# buffered-mult.net
KiCad netlist of a schematic drawn in EAGLE
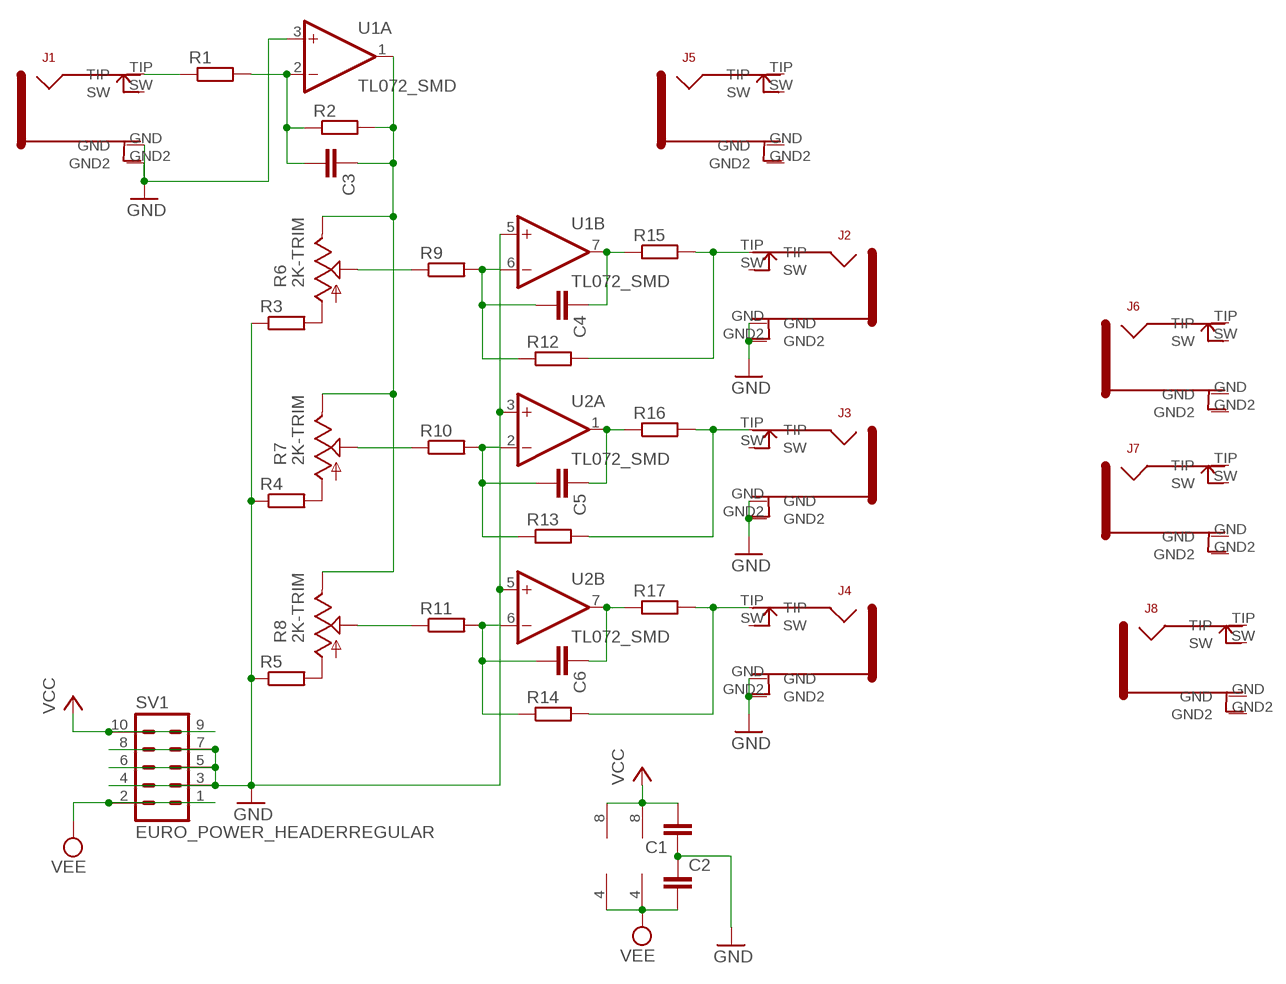
[diagram p0: schematic, sheet 1]

(export (version "E")
  (design (tool "Eeschema 10.0.6"))
  (components
    (comp (ref "C1")
      (value "C-EUC0603")
      (footprint "eagle-import:C0603")
      (libsource (lib "eagle-import") (part "C-EUC0603"))
    )
    (comp (ref "C2")
      (value "C-EUC0603")
      (footprint "eagle-import:C0603")
      (libsource (lib "eagle-import") (part "C-EUC0603"))
    )
    (comp (ref "C3")
      (value "C-EUC0603")
      (footprint "eagle-import:C0603")
      (libsource (lib "eagle-import") (part "C-EUC0603"))
    )
    (comp (ref "C4")
      (value "C-EUC0603")
      (footprint "eagle-import:C0603")
      (libsource (lib "eagle-import") (part "C-EUC0603"))
    )
    (comp (ref "C5")
      (value "C-EUC0603")
      (footprint "eagle-import:C0603")
      (libsource (lib "eagle-import") (part "C-EUC0603"))
    )
    (comp (ref "C6")
      (value "C-EUC0603")
      (footprint "eagle-import:C0603")
      (libsource (lib "eagle-import") (part "C-EUC0603"))
    )
    (comp (ref "J1")
      (value "WQP_PJ_301BM")
      (footprint "eagle-import:WQP_PJ_301BM")
      (libsource (lib "eagle-import") (part "WQP_PJ_301BM"))
    )
    (comp (ref "J2")
      (value "WQP_PJ_301BM")
      (footprint "eagle-import:WQP_PJ_301BM")
      (libsource (lib "eagle-import") (part "WQP_PJ_301BM"))
    )
    (comp (ref "J3")
      (value "WQP_PJ_301BM")
      (footprint "eagle-import:WQP_PJ_301BM")
      (libsource (lib "eagle-import") (part "WQP_PJ_301BM"))
    )
    (comp (ref "J4")
      (value "WQP_PJ_301BM")
      (footprint "eagle-import:WQP_PJ_301BM")
      (libsource (lib "eagle-import") (part "WQP_PJ_301BM"))
    )
    (comp (ref "J5")
      (value "WQP_PJ_301BM")
      (footprint "eagle-import:WQP_PJ_301BM")
      (libsource (lib "eagle-import") (part "WQP_PJ_301BM"))
    )
    (comp (ref "J6")
      (value "WQP_PJ_301BM")
      (footprint "eagle-import:WQP_PJ_301BM")
      (libsource (lib "eagle-import") (part "WQP_PJ_301BM"))
    )
    (comp (ref "J7")
      (value "WQP_PJ_301BM")
      (footprint "eagle-import:WQP_PJ_301BM")
      (libsource (lib "eagle-import") (part "WQP_PJ_301BM"))
    )
    (comp (ref "J8")
      (value "WQP_PJ_301BM")
      (footprint "eagle-import:WQP_PJ_301BM")
      (libsource (lib "eagle-import") (part "WQP_PJ_301BM"))
    )
    (comp (ref "R1")
      (value "R-EU_R0603")
      (footprint "eagle-import:R0603")
      (libsource (lib "eagle-import") (part "R-EU_R0603"))
    )
    (comp (ref "R2")
      (value "R-EU_R0603")
      (footprint "eagle-import:R0603")
      (libsource (lib "eagle-import") (part "R-EU_R0603"))
    )
    (comp (ref "R3")
      (value "R-EU_R0603")
      (footprint "eagle-import:R0603")
      (libsource (lib "eagle-import") (part "R-EU_R0603"))
    )
    (comp (ref "R4")
      (value "R-EU_R0603")
      (footprint "eagle-import:R0603")
      (libsource (lib "eagle-import") (part "R-EU_R0603"))
    )
    (comp (ref "R5")
      (value "R-EU_R0603")
      (footprint "eagle-import:R0603")
      (libsource (lib "eagle-import") (part "R-EU_R0603"))
    )
    (comp (ref "R6")
      (value "2K-TRIM")
      (footprint "eagle-import:BOURNS_TRIM_3303X3_SMD")
      (libsource (lib "eagle-import") (part "BOURNS_TRIM_3303X3_SMD"))
    )
    (comp (ref "R7")
      (value "2K-TRIM")
      (footprint "eagle-import:BOURNS_TRIM_3303X3_SMD")
      (libsource (lib "eagle-import") (part "BOURNS_TRIM_3303X3_SMD"))
    )
    (comp (ref "R8")
      (value "2K-TRIM")
      (footprint "eagle-import:BOURNS_TRIM_3303X3_SMD")
      (libsource (lib "eagle-import") (part "BOURNS_TRIM_3303X3_SMD"))
    )
    (comp (ref "R9")
      (value "R-EU_R0603")
      (footprint "eagle-import:R0603")
      (libsource (lib "eagle-import") (part "R-EU_R0603"))
    )
    (comp (ref "R10")
      (value "R-EU_R0603")
      (footprint "eagle-import:R0603")
      (libsource (lib "eagle-import") (part "R-EU_R0603"))
    )
    (comp (ref "R11")
      (value "R-EU_R0603")
      (footprint "eagle-import:R0603")
      (libsource (lib "eagle-import") (part "R-EU_R0603"))
    )
    (comp (ref "R12")
      (value "R-EU_R0603")
      (footprint "eagle-import:R0603")
      (libsource (lib "eagle-import") (part "R-EU_R0603"))
    )
    (comp (ref "R13")
      (value "R-EU_R0603")
      (footprint "eagle-import:R0603")
      (libsource (lib "eagle-import") (part "R-EU_R0603"))
    )
    (comp (ref "R14")
      (value "R-EU_R0603")
      (footprint "eagle-import:R0603")
      (libsource (lib "eagle-import") (part "R-EU_R0603"))
    )
    (comp (ref "R15")
      (value "R-EU_R0603")
      (footprint "eagle-import:R0603")
      (libsource (lib "eagle-import") (part "R-EU_R0603"))
    )
    (comp (ref "R16")
      (value "R-EU_R0603")
      (footprint "eagle-import:R0603")
      (libsource (lib "eagle-import") (part "R-EU_R0603"))
    )
    (comp (ref "R17")
      (value "R-EU_R0603")
      (footprint "eagle-import:R0603")
      (libsource (lib "eagle-import") (part "R-EU_R0603"))
    )
    (comp (ref "SV1")
      (value "EURO_POWER_HEADERREGULAR")
      (footprint "eagle-import:EURO_POWER_HEADER")
      (libsource (lib "eagle-import") (part "EURO_POWER_HEADERREGULAR"))
    )
    (comp (ref "U1")
      (value "TL072_SMD")
      (footprint "eagle-import:SO08")
      (libsource (lib "eagle-import") (part "TL072_SMD"))
    )
    (comp (ref "U2")
      (value "TL072_SMD")
      (footprint "eagle-import:SO08")
      (libsource (lib "eagle-import") (part "TL072_SMD"))
    )
  )
  (nets
    (net (code "1") (name "GND") (class "Default")
      (node (ref "C1") (pin "1") (pinfunction "1_1") (pintype "passive"))
      (node (ref "C2") (pin "1") (pinfunction "1_1") (pintype "passive"))
      (node (ref "J1") (pin "GND") (pinfunction "GND_GND") (pintype "passive"))
      (node (ref "J1") (pin "GND2") (pinfunction "GND2_GND2") (pintype "passive"))
      (node (ref "J2") (pin "GND") (pinfunction "GND_GND") (pintype "passive"))
      (node (ref "J2") (pin "GND2") (pinfunction "GND2_GND2") (pintype "passive"))
      (node (ref "J3") (pin "GND") (pinfunction "GND_GND") (pintype "passive"))
      (node (ref "J3") (pin "GND2") (pinfunction "GND2_GND2") (pintype "passive"))
      (node (ref "J4") (pin "GND") (pinfunction "GND_GND") (pintype "passive"))
      (node (ref "J4") (pin "GND2") (pinfunction "GND2_GND2") (pintype "passive"))
      (node (ref "R3") (pin "1") (pinfunction "1_1") (pintype "passive"))
      (node (ref "R4") (pin "1") (pinfunction "1_1") (pintype "passive"))
      (node (ref "R5") (pin "1") (pinfunction "1_1") (pintype "passive"))
      (node (ref "SV1") (pin "3") (pinfunction "3_3") (pintype "passive"))
      (node (ref "SV1") (pin "4") (pinfunction "4_4") (pintype "passive"))
      (node (ref "SV1") (pin "5") (pinfunction "5_5") (pintype "passive"))
      (node (ref "SV1") (pin "6") (pinfunction "6_6") (pintype "passive"))
      (node (ref "SV1") (pin "7") (pinfunction "7_7") (pintype "passive"))
      (node (ref "SV1") (pin "8") (pinfunction "8_8") (pintype "passive"))
      (node (ref "U1") (pin "3") (pinfunction "+IN_3") (pintype "input"))
      (node (ref "U1") (pin "5") (pinfunction "+IN_5") (pintype "input"))
      (node (ref "U2") (pin "3") (pinfunction "+IN_3") (pintype "input"))
      (node (ref "U2") (pin "5") (pinfunction "+IN_5") (pintype "input"))
    )
    (net (code "2") (name "Net-(J1-PadTIP)") (class "Default")
      (node (ref "J1") (pin "TIP") (pinfunction "TIP_TIP") (pintype "passive"))
      (node (ref "R1") (pin "1") (pinfunction "1_1") (pintype "passive"))
    )
    (net (code "3") (name "Net-(J2-PadTIP)") (class "Default")
      (node (ref "J2") (pin "TIP") (pinfunction "TIP_TIP") (pintype "passive"))
      (node (ref "R12") (pin "2") (pinfunction "2_2") (pintype "passive"))
      (node (ref "R15") (pin "2") (pinfunction "2_2") (pintype "passive"))
    )
    (net (code "4") (name "Net-(J3-PadTIP)") (class "Default")
      (node (ref "J3") (pin "TIP") (pinfunction "TIP_TIP") (pintype "passive"))
      (node (ref "R13") (pin "2") (pinfunction "2_2") (pintype "passive"))
      (node (ref "R16") (pin "2") (pinfunction "2_2") (pintype "passive"))
    )
    (net (code "5") (name "Net-(J4-PadTIP)") (class "Default")
      (node (ref "J4") (pin "TIP") (pinfunction "TIP_TIP") (pintype "passive"))
      (node (ref "R14") (pin "2") (pinfunction "2_2") (pintype "passive"))
      (node (ref "R17") (pin "2") (pinfunction "2_2") (pintype "passive"))
    )
    (net (code "6") (name "Net-(R6-A)") (class "Default")
      (node (ref "R3") (pin "2") (pinfunction "2_2") (pintype "passive"))
      (node (ref "R6") (pin "3") (pinfunction "A_3") (pintype "passive"))
    )
    (net (code "7") (name "Net-(R6-E)") (class "Default")
      (node (ref "C3") (pin "1") (pinfunction "1_1") (pintype "passive"))
      (node (ref "R2") (pin "2") (pinfunction "2_2") (pintype "passive"))
      (node (ref "R6") (pin "1") (pinfunction "E_1") (pintype "passive"))
      (node (ref "R7") (pin "1") (pinfunction "E_1") (pintype "passive"))
      (node (ref "R8") (pin "1") (pinfunction "E_1") (pintype "passive"))
      (node (ref "U1") (pin "1") (pinfunction "OUT_1") (pintype "output"))
    )
    (net (code "8") (name "Net-(R6-S)") (class "Default")
      (node (ref "R6") (pin "2") (pinfunction "S_2") (pintype "passive"))
      (node (ref "R9") (pin "1") (pinfunction "1_1") (pintype "passive"))
    )
    (net (code "9") (name "Net-(R7-A)") (class "Default")
      (node (ref "R4") (pin "2") (pinfunction "2_2") (pintype "passive"))
      (node (ref "R7") (pin "3") (pinfunction "A_3") (pintype "passive"))
    )
    (net (code "10") (name "Net-(R7-S)") (class "Default")
      (node (ref "R10") (pin "1") (pinfunction "1_1") (pintype "passive"))
      (node (ref "R7") (pin "2") (pinfunction "S_2") (pintype "passive"))
    )
    (net (code "11") (name "Net-(R8-A)") (class "Default")
      (node (ref "R5") (pin "2") (pinfunction "2_2") (pintype "passive"))
      (node (ref "R8") (pin "3") (pinfunction "A_3") (pintype "passive"))
    )
    (net (code "12") (name "Net-(R8-S)") (class "Default")
      (node (ref "R11") (pin "1") (pinfunction "1_1") (pintype "passive"))
      (node (ref "R8") (pin "2") (pinfunction "S_2") (pintype "passive"))
    )
    (net (code "13") (name "Net-(U1A--IN)") (class "Default")
      (node (ref "C3") (pin "2") (pinfunction "2_2") (pintype "passive"))
      (node (ref "R1") (pin "2") (pinfunction "2_2") (pintype "passive"))
      (node (ref "R2") (pin "1") (pinfunction "1_1") (pintype "passive"))
      (node (ref "U1") (pin "2") (pinfunction "-IN_2") (pintype "input"))
    )
    (net (code "14") (name "Net-(U1B--IN)") (class "Default")
      (node (ref "C4") (pin "2") (pinfunction "2_2") (pintype "passive"))
      (node (ref "R12") (pin "1") (pinfunction "1_1") (pintype "passive"))
      (node (ref "R9") (pin "2") (pinfunction "2_2") (pintype "passive"))
      (node (ref "U1") (pin "6") (pinfunction "-IN_6") (pintype "input"))
    )
    (net (code "15") (name "Net-(U1B-OUT)") (class "Default")
      (node (ref "C4") (pin "1") (pinfunction "1_1") (pintype "passive"))
      (node (ref "R15") (pin "1") (pinfunction "1_1") (pintype "passive"))
      (node (ref "U1") (pin "7") (pinfunction "OUT_7") (pintype "output"))
    )
    (net (code "16") (name "Net-(U2A--IN)") (class "Default")
      (node (ref "C5") (pin "2") (pinfunction "2_2") (pintype "passive"))
      (node (ref "R10") (pin "2") (pinfunction "2_2") (pintype "passive"))
      (node (ref "R13") (pin "1") (pinfunction "1_1") (pintype "passive"))
      (node (ref "U2") (pin "2") (pinfunction "-IN_2") (pintype "input"))
    )
    (net (code "17") (name "Net-(U2A-OUT)") (class "Default")
      (node (ref "C5") (pin "1") (pinfunction "1_1") (pintype "passive"))
      (node (ref "R16") (pin "1") (pinfunction "1_1") (pintype "passive"))
      (node (ref "U2") (pin "1") (pinfunction "OUT_1") (pintype "output"))
    )
    (net (code "18") (name "Net-(U2B--IN)") (class "Default")
      (node (ref "C6") (pin "2") (pinfunction "2_2") (pintype "passive"))
      (node (ref "R11") (pin "2") (pinfunction "2_2") (pintype "passive"))
      (node (ref "R14") (pin "1") (pinfunction "1_1") (pintype "passive"))
      (node (ref "U2") (pin "6") (pinfunction "-IN_6") (pintype "input"))
    )
    (net (code "19") (name "Net-(U2B-OUT)") (class "Default")
      (node (ref "C6") (pin "1") (pinfunction "1_1") (pintype "passive"))
      (node (ref "R17") (pin "1") (pinfunction "1_1") (pintype "passive"))
      (node (ref "U2") (pin "7") (pinfunction "OUT_7") (pintype "output"))
    )
    (net (code "20") (name "VCC") (class "Default")
      (node (ref "C1") (pin "2") (pinfunction "2_2") (pintype "passive"))
      (node (ref "SV1") (pin "10") (pinfunction "10_10") (pintype "passive"))
      (node (ref "SV1") (pin "9") (pinfunction "9_9") (pintype "passive"))
      (node (ref "U1") (pin "8") (pinfunction "V+_8") (pintype "power_in"))
      (node (ref "U2") (pin "8") (pinfunction "V+_8") (pintype "power_in"))
    )
    (net (code "21") (name "VEE") (class "Default")
      (node (ref "C2") (pin "2") (pinfunction "2_2") (pintype "passive"))
      (node (ref "SV1") (pin "1") (pinfunction "1_1") (pintype "passive"))
      (node (ref "SV1") (pin "2") (pinfunction "2_2") (pintype "passive"))
      (node (ref "U1") (pin "4") (pinfunction "V-_4") (pintype "power_in"))
      (node (ref "U2") (pin "4") (pinfunction "V-_4") (pintype "power_in"))
    )
    (net (code "22") (name "unconnected-(J1-PadSW)") (class "Default")
      (node (ref "J1") (pin "SW") (pinfunction "SW_SW") (pintype "passive"))
    )
    (net (code "23") (name "unconnected-(J2-PadSW)") (class "Default")
      (node (ref "J2") (pin "SW") (pinfunction "SW_SW") (pintype "passive"))
    )
    (net (code "24") (name "unconnected-(J3-PadSW)") (class "Default")
      (node (ref "J3") (pin "SW") (pinfunction "SW_SW") (pintype "passive"))
    )
    (net (code "25") (name "unconnected-(J4-PadSW)") (class "Default")
      (node (ref "J4") (pin "SW") (pinfunction "SW_SW") (pintype "passive"))
    )
    (net (code "26") (name "unconnected-(J5-PadGND)") (class "Default")
      (node (ref "J5") (pin "GND") (pinfunction "GND_GND") (pintype "passive"))
    )
    (net (code "27") (name "unconnected-(J5-PadGND2)") (class "Default")
      (node (ref "J5") (pin "GND2") (pinfunction "GND2_GND2") (pintype "passive"))
    )
    (net (code "28") (name "unconnected-(J5-PadSW)") (class "Default")
      (node (ref "J5") (pin "SW") (pinfunction "SW_SW") (pintype "passive"))
    )
    (net (code "29") (name "unconnected-(J5-PadTIP)") (class "Default")
      (node (ref "J5") (pin "TIP") (pinfunction "TIP_TIP") (pintype "passive"))
    )
    (net (code "30") (name "unconnected-(J6-PadGND)") (class "Default")
      (node (ref "J6") (pin "GND") (pinfunction "GND_GND") (pintype "passive"))
    )
    (net (code "31") (name "unconnected-(J6-PadGND2)") (class "Default")
      (node (ref "J6") (pin "GND2") (pinfunction "GND2_GND2") (pintype "passive"))
    )
    (net (code "32") (name "unconnected-(J6-PadSW)") (class "Default")
      (node (ref "J6") (pin "SW") (pinfunction "SW_SW") (pintype "passive"))
    )
    (net (code "33") (name "unconnected-(J6-PadTIP)") (class "Default")
      (node (ref "J6") (pin "TIP") (pinfunction "TIP_TIP") (pintype "passive"))
    )
    (net (code "34") (name "unconnected-(J7-PadGND)") (class "Default")
      (node (ref "J7") (pin "GND") (pinfunction "GND_GND") (pintype "passive"))
    )
    (net (code "35") (name "unconnected-(J7-PadGND2)") (class "Default")
      (node (ref "J7") (pin "GND2") (pinfunction "GND2_GND2") (pintype "passive"))
    )
    (net (code "36") (name "unconnected-(J7-PadSW)") (class "Default")
      (node (ref "J7") (pin "SW") (pinfunction "SW_SW") (pintype "passive"))
    )
    (net (code "37") (name "unconnected-(J7-PadTIP)") (class "Default")
      (node (ref "J7") (pin "TIP") (pinfunction "TIP_TIP") (pintype "passive"))
    )
    (net (code "38") (name "unconnected-(J8-PadGND)") (class "Default")
      (node (ref "J8") (pin "GND") (pinfunction "GND_GND") (pintype "passive"))
    )
    (net (code "39") (name "unconnected-(J8-PadGND2)") (class "Default")
      (node (ref "J8") (pin "GND2") (pinfunction "GND2_GND2") (pintype "passive"))
    )
    (net (code "40") (name "unconnected-(J8-PadSW)") (class "Default")
      (node (ref "J8") (pin "SW") (pinfunction "SW_SW") (pintype "passive"))
    )
    (net (code "41") (name "unconnected-(J8-PadTIP)") (class "Default")
      (node (ref "J8") (pin "TIP") (pinfunction "TIP_TIP") (pintype "passive"))
    )
  )
)
